# schematic.net
KiCad netlist of a schematic drawn in EasyEDA
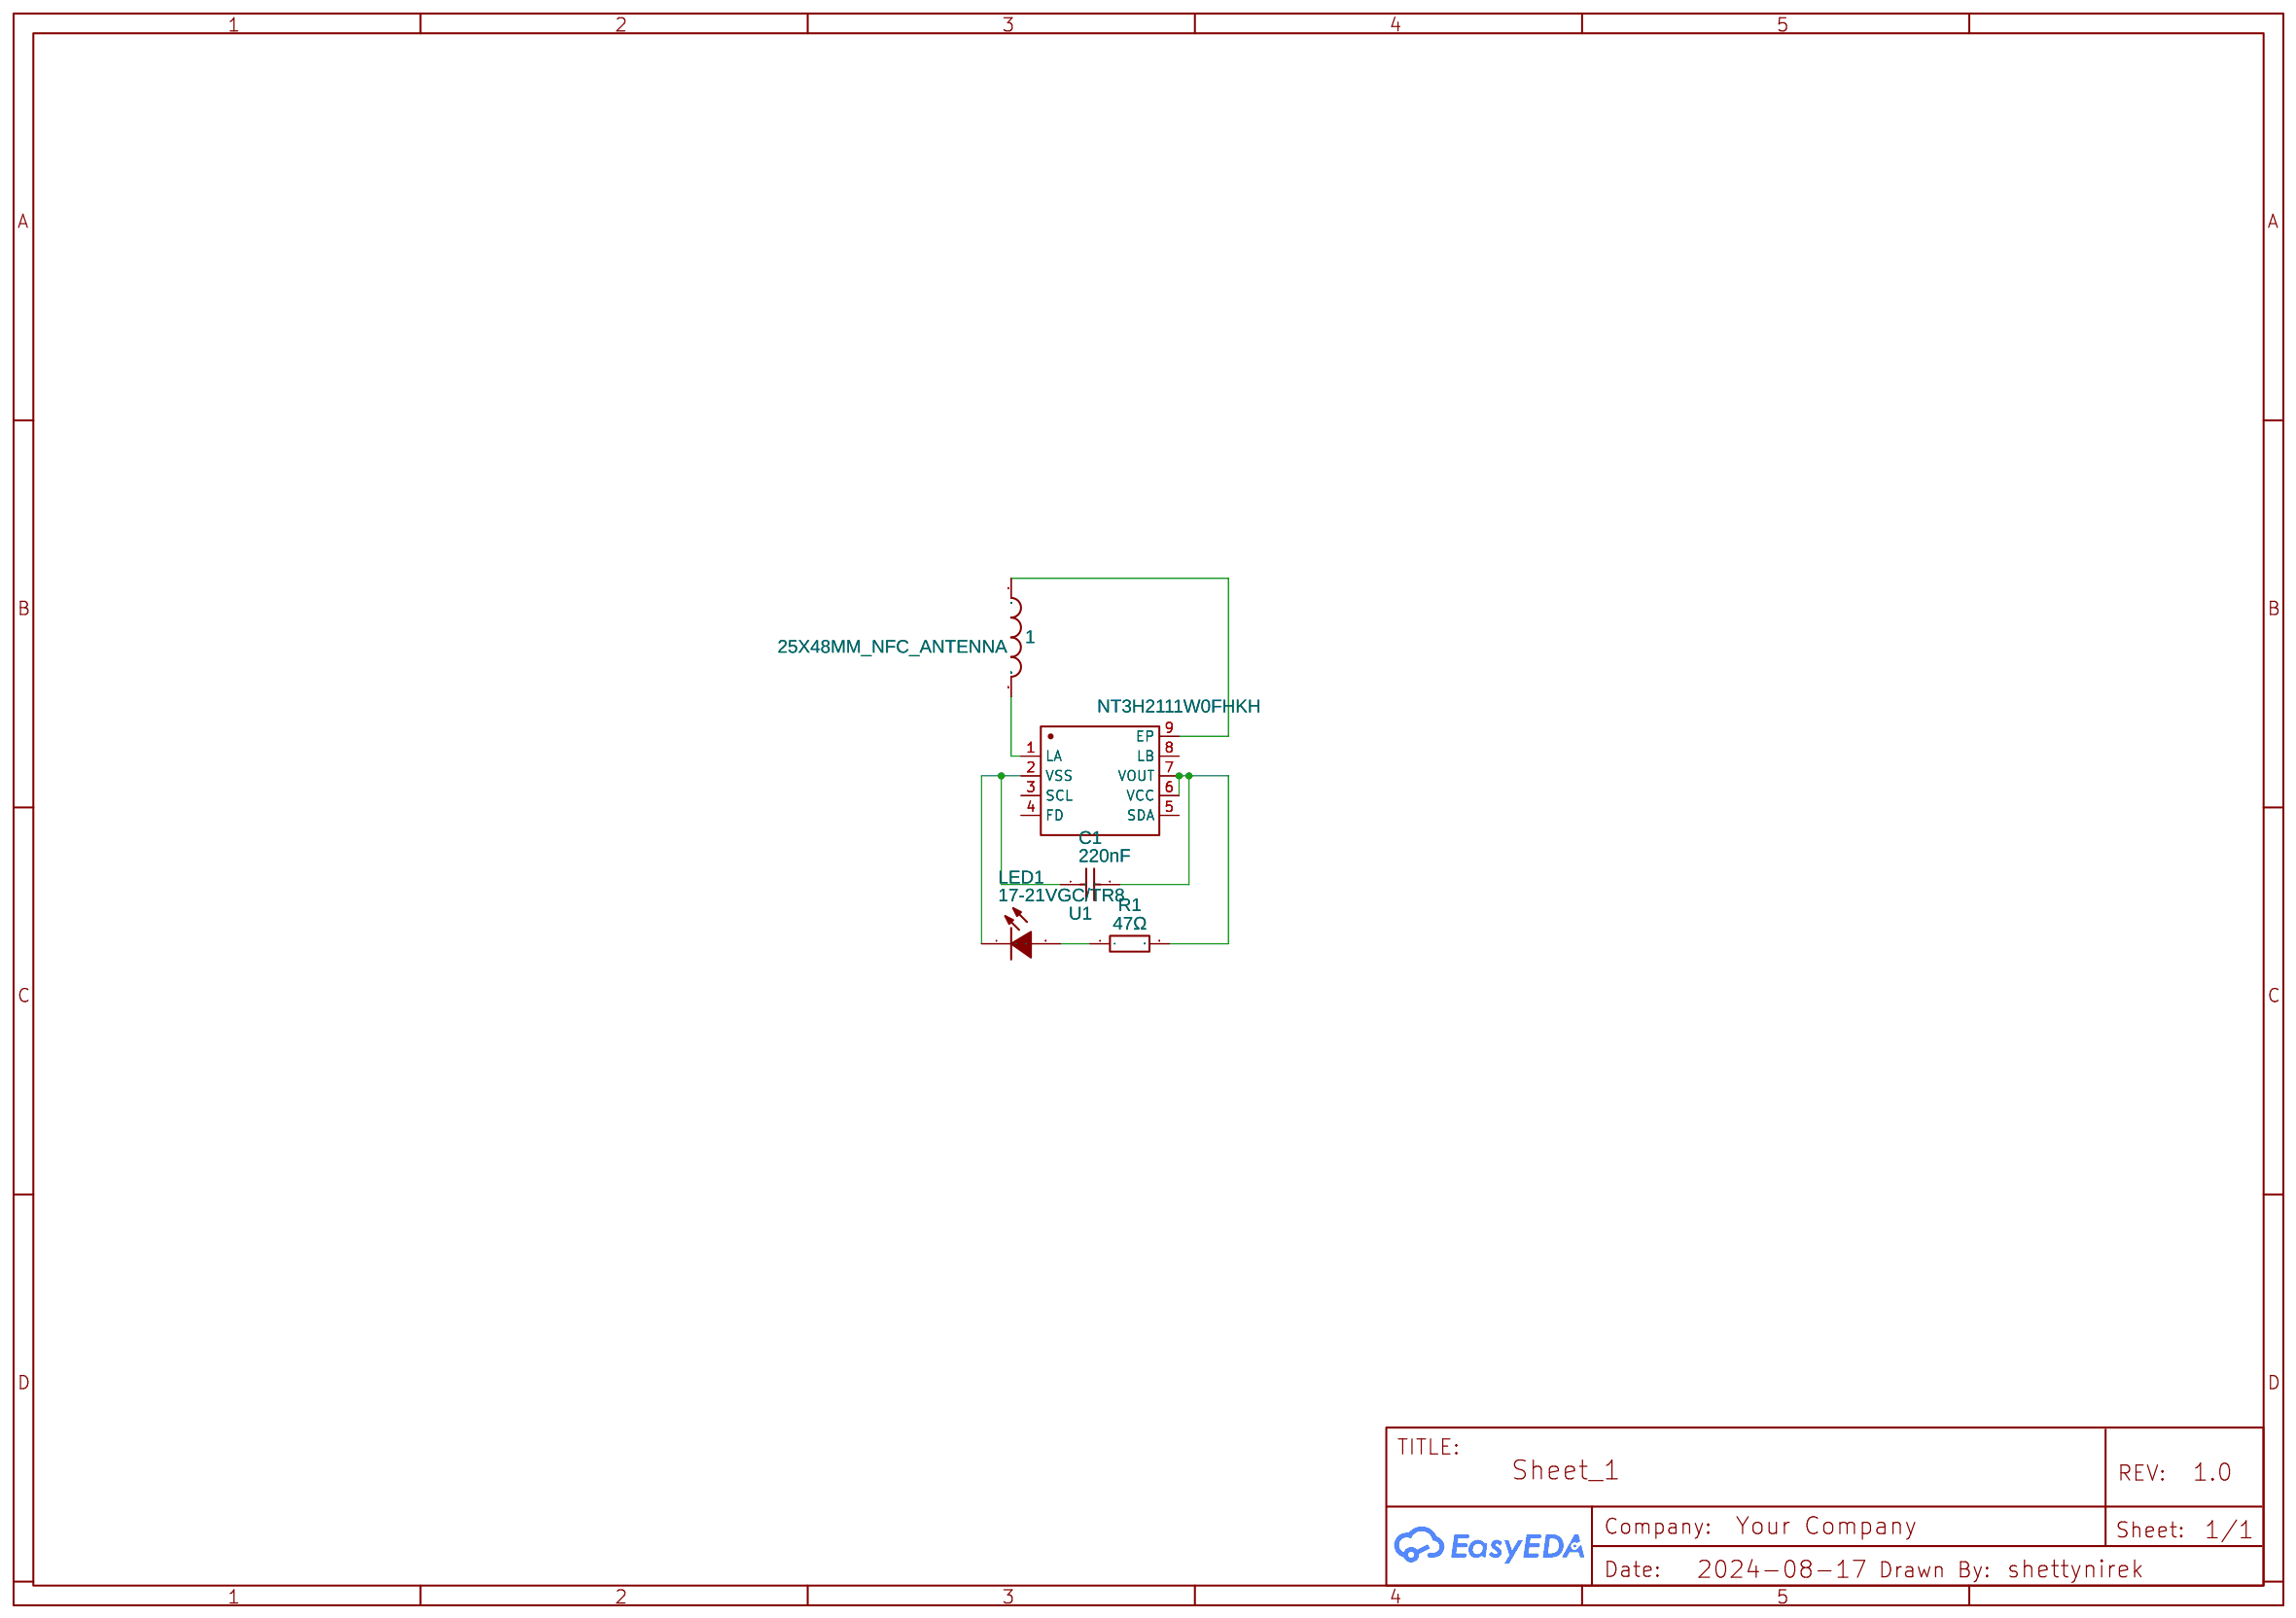
[diagram p0: schematic sheet]

(export (version "E")
  (design (tool "Eeschema 10.0.6"))
  (components
    (comp (ref "1") (value "25X48MM_NFC_ANTENNA") (libsource (lib "") (part "25X48MM_NFC_ANTENNA")))
    (comp (ref "C1")
      (value "220nF")
      (fields
        (field (name "Manufacturer Part") "CL10B224KA8NNNC")
        (field (name "Manufacturer") "SAMSUNG(三星)")
      )
      (libsource (lib "") (part "CL10B224KA8NNNC"))
    )
    (comp (ref "LED1")
      (value "17-21VGC/TR8")
      (fields (field (name "Manufacturer") "EVERLIGHT(亿光)"))
      (libsource (lib "") (part "17-21VGC/TR8"))
    )
    (comp (ref "R1")
      (value "47Ω")
      (fields
        (field (name "Manufacturer Part") "0603WAF470JT5E")
        (field (name "Manufacturer") "UNI-ROYAL(厚声)")
      )
      (libsource (lib "") (part "0603WAF470JT5E"))
    )
    (comp (ref "U1")
      (value "NT3H2111W0FHKH")
      (fields (field (name "Manufacturer") "NXP(恩智浦)"))
      (libsource (lib "") (part "NT3H2111W0FHKH"))
    )
  )
  (nets
    (net (code "1") (name "Net-(LED1-+)") (class "Default")
      (node (ref "LED1") (pin "2") (pinfunction "+_2") (pintype "unspecified"))
      (node (ref "R1") (pin "1") (pinfunction "1_1") (pintype "input"))
    )
    (net (code "2") (name "Net-(LED1--)") (class "Default")
      (node (ref "C1") (pin "1") (pinfunction "1_1") (pintype "input"))
      (node (ref "LED1") (pin "1") (pinfunction "-_1") (pintype "unspecified"))
      (node (ref "U1") (pin "2") (pinfunction "VSS_2") (pintype "unspecified"))
    )
    (net (code "3") (name "Net-(U1-EP)") (class "Default")
      (node (ref "1") (pin "P$1") (pinfunction "P$1_P$1") (pintype "bidirectional"))
      (node (ref "U1") (pin "9") (pinfunction "EP_9") (pintype "unspecified"))
    )
    (net (code "4") (name "Net-(U1-LA)") (class "Default")
      (node (ref "1") (pin "P$2") (pinfunction "P$2_P$2") (pintype "bidirectional"))
      (node (ref "U1") (pin "1") (pinfunction "LA_1") (pintype "unspecified"))
    )
    (net (code "5") (name "Net-(U1-VCC)") (class "Default")
      (node (ref "C1") (pin "2") (pinfunction "2_2") (pintype "input"))
      (node (ref "R1") (pin "2") (pinfunction "2_2") (pintype "input"))
      (node (ref "U1") (pin "6") (pinfunction "VCC_6") (pintype "unspecified"))
      (node (ref "U1") (pin "7") (pinfunction "VOUT_7") (pintype "unspecified"))
    )
    (net (code "6") (name "unconnected-(U1-FD-Pad4)") (class "Default")
      (node (ref "U1") (pin "4") (pinfunction "FD_4") (pintype "unspecified"))
    )
    (net (code "7") (name "unconnected-(U1-LB-Pad8)") (class "Default")
      (node (ref "U1") (pin "8") (pinfunction "LB_8") (pintype "unspecified"))
    )
    (net (code "8") (name "unconnected-(U1-SCL-Pad3)") (class "Default")
      (node (ref "U1") (pin "3") (pinfunction "SCL_3") (pintype "unspecified"))
    )
    (net (code "9") (name "unconnected-(U1-SDA-Pad5)") (class "Default")
      (node (ref "U1") (pin "5") (pinfunction "SDA_5") (pintype "unspecified"))
    )
  )
)
